# main.net
KiCad netlist of a schematic drawn in Altium Designer
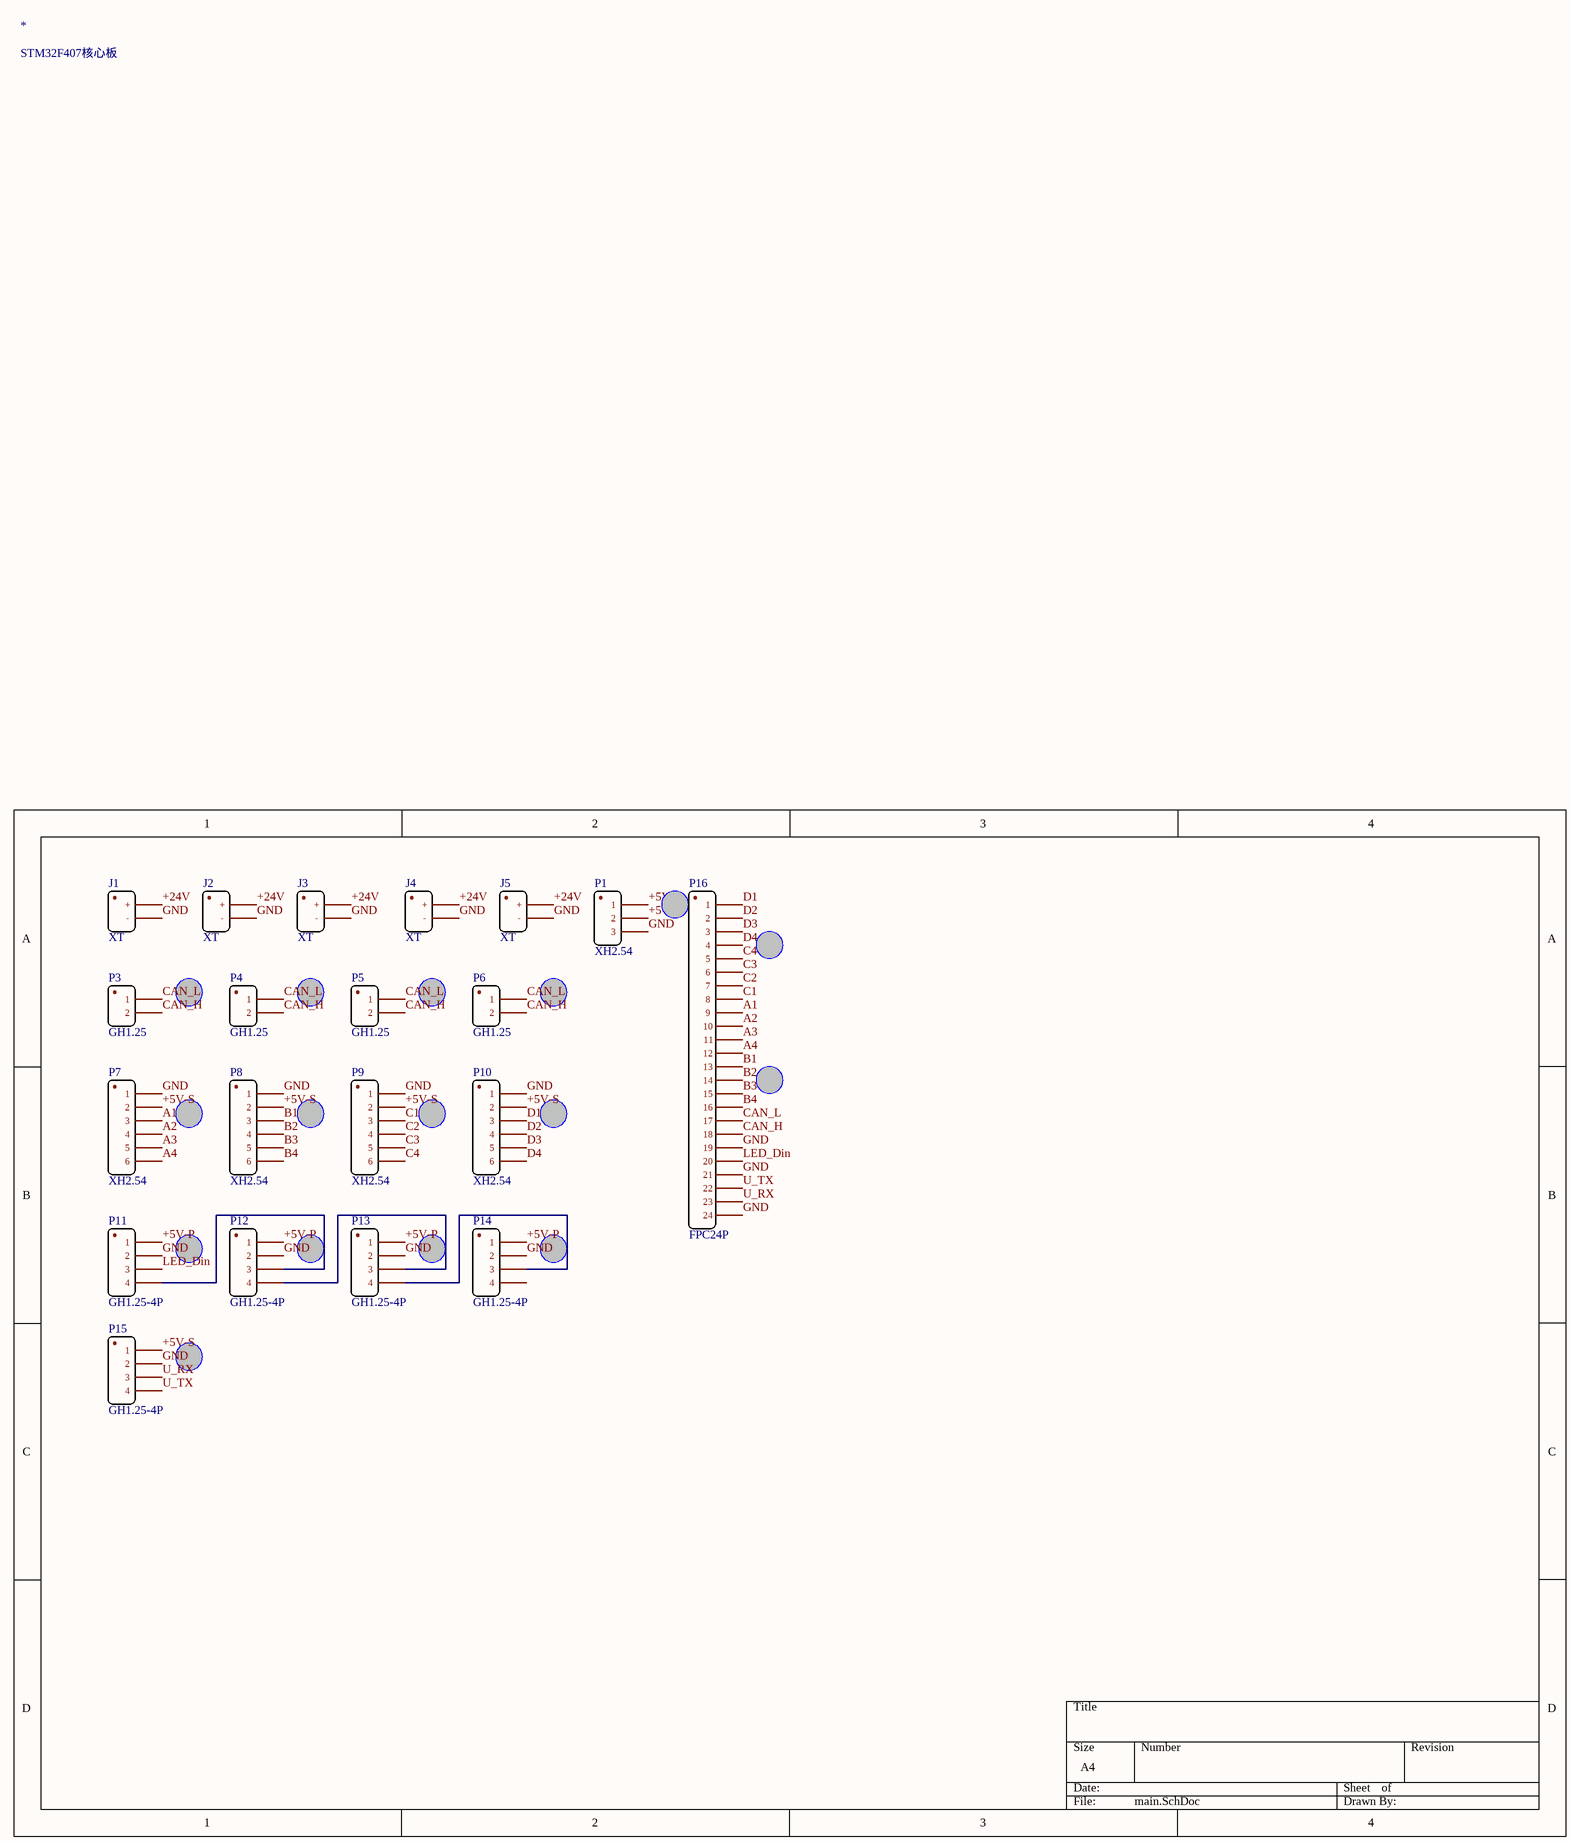
[diagram p0: main.SchDoc]

(export (version "E")
  (design (tool "Eeschema 10.0.6"))
  (components
    (comp (ref "*") (value "STM32F407核心板") (libsource (lib "模块库原理图") (part "STM32F407核心板")))
    (comp (ref "J1") (value "XT") (footprint "XT30-PW-F") (libsource (lib "接口库") (part "接口_XT")))
    (comp (ref "J2") (value "XT") (footprint "XT30-PW-F") (libsource (lib "接口库") (part "接口_XT")))
    (comp (ref "J3") (value "XT") (footprint "XT30-PW-F") (libsource (lib "接口库") (part "接口_XT")))
    (comp (ref "J4") (value "XT") (footprint "XT30-PW-F") (libsource (lib "接口库") (part "接口_XT")))
    (comp (ref "J5") (value "XT") (footprint "XT30-PW-M") (libsource (lib "接口库") (part "接口_XT")))
    (comp (ref "P1") (value "XH2.54") (footprint "XH2.54-PB-1*3") (libsource (lib "接口库") (part "接插件1*3")))
    (comp (ref "P3") (value "GH1.25") (footprint "GH1.25-PW-1*2") (libsource (lib "接口库") (part "接插件1*2")))
    (comp (ref "P4") (value "GH1.25") (footprint "GH1.25-PW-1*2") (libsource (lib "接口库") (part "接插件1*2")))
    (comp (ref "P5") (value "GH1.25") (footprint "GH1.25-PW-1*2") (libsource (lib "接口库") (part "接插件1*2")))
    (comp (ref "P6") (value "GH1.25") (footprint "GH1.25-PW-1*2") (libsource (lib "接口库") (part "接插件1*2")))
    (comp (ref "P7") (value "XH2.54") (footprint "XH2.54_AW_1*6") (libsource (lib "接口库") (part "接插件1*6")))
    (comp (ref "P8") (value "XH2.54") (footprint "XH2.54_AW_1*6") (libsource (lib "接口库") (part "接插件1*6")))
    (comp (ref "P9") (value "XH2.54") (footprint "XH2.54_AW_1*6") (libsource (lib "接口库") (part "接插件1*6")))
    (comp (ref "P10") (value "XH2.54") (footprint "XH2.54_AW_1*6") (libsource (lib "接口库") (part "接插件1*6")))
    (comp (ref "P11") (value "GH1.25-4P") (footprint "GH1.25-PW-1*4") (libsource (lib "接口库") (part "接插件1*4")))
    (comp (ref "P12") (value "GH1.25-4P") (footprint "GH1.25-PW-1*4") (libsource (lib "接口库") (part "接插件1*4")))
    (comp (ref "P13") (value "GH1.25-4P") (footprint "GH1.25-PW-1*4") (libsource (lib "接口库") (part "接插件1*4")))
    (comp (ref "P14") (value "GH1.25-4P") (footprint "GH1.25-PW-1*4") (libsource (lib "接口库") (part "接插件1*4")))
    (comp (ref "P15") (value "GH1.25-4P") (footprint "GH1.25-PW-1*4") (libsource (lib "接口库") (part "接插件1*4")))
    (comp (ref "P16") (value "FPC24P") (footprint "FPC0.5-WT-24P") (libsource (lib "接口库") (part "接插件1*24")))
  )
  (nets
    (net (code "1") (name "/+5V-P") (class "Default")
      (node (ref "P1") (pin "2") (pinfunction "2_2") (pintype "passive"))
      (node (ref "P11") (pin "1") (pinfunction "1_1") (pintype "passive"))
      (node (ref "P12") (pin "1") (pinfunction "1_1") (pintype "passive"))
      (node (ref "P13") (pin "1") (pinfunction "1_1") (pintype "passive"))
      (node (ref "P14") (pin "1") (pinfunction "1_1") (pintype "passive"))
    )
    (net (code "2") (name "/+5V-S") (class "Default")
      (node (ref "P1") (pin "1") (pinfunction "1_1") (pintype "passive"))
      (node (ref "P10") (pin "2") (pinfunction "2_2") (pintype "passive"))
      (node (ref "P15") (pin "1") (pinfunction "1_1") (pintype "passive"))
      (node (ref "P7") (pin "2") (pinfunction "2_2") (pintype "passive"))
      (node (ref "P8") (pin "2") (pinfunction "2_2") (pintype "passive"))
      (node (ref "P9") (pin "2") (pinfunction "2_2") (pintype "passive"))
    )
    (net (code "3") (name "/+24V") (class "Default")
      (node (ref "J1") (pin "1") (pinfunction "1_1") (pintype "passive"))
      (node (ref "J2") (pin "1") (pinfunction "1_1") (pintype "passive"))
      (node (ref "J3") (pin "1") (pinfunction "1_1") (pintype "passive"))
      (node (ref "J4") (pin "1") (pinfunction "1_1") (pintype "passive"))
      (node (ref "J5") (pin "1") (pinfunction "1_1") (pintype "passive"))
    )
    (net (code "4") (name "/A1") (class "Default")
      (node (ref "P16") (pin "9") (pinfunction "9_9") (pintype "passive"))
      (node (ref "P7") (pin "3") (pinfunction "3_3") (pintype "passive"))
    )
    (net (code "5") (name "/A2") (class "Default")
      (node (ref "P16") (pin "10") (pinfunction "10_10") (pintype "passive"))
      (node (ref "P7") (pin "4") (pinfunction "4_4") (pintype "passive"))
    )
    (net (code "6") (name "/A3") (class "Default")
      (node (ref "P16") (pin "11") (pinfunction "11_11") (pintype "passive"))
      (node (ref "P7") (pin "5") (pinfunction "5_5") (pintype "passive"))
    )
    (net (code "7") (name "/A4") (class "Default")
      (node (ref "P16") (pin "12") (pinfunction "12_12") (pintype "passive"))
      (node (ref "P7") (pin "6") (pinfunction "6_6") (pintype "passive"))
    )
    (net (code "8") (name "/B1") (class "Default")
      (node (ref "P16") (pin "13") (pinfunction "13_13") (pintype "passive"))
      (node (ref "P8") (pin "3") (pinfunction "3_3") (pintype "passive"))
    )
    (net (code "9") (name "/B2") (class "Default")
      (node (ref "P16") (pin "14") (pinfunction "14_14") (pintype "passive"))
      (node (ref "P8") (pin "4") (pinfunction "4_4") (pintype "passive"))
    )
    (net (code "10") (name "/B3") (class "Default")
      (node (ref "P16") (pin "15") (pinfunction "15_15") (pintype "passive"))
      (node (ref "P8") (pin "5") (pinfunction "5_5") (pintype "passive"))
    )
    (net (code "11") (name "/B4") (class "Default")
      (node (ref "P16") (pin "16") (pinfunction "16_16") (pintype "passive"))
      (node (ref "P8") (pin "6") (pinfunction "6_6") (pintype "passive"))
    )
    (net (code "12") (name "/C1") (class "Default")
      (node (ref "P16") (pin "8") (pinfunction "8_8") (pintype "passive"))
      (node (ref "P9") (pin "3") (pinfunction "3_3") (pintype "passive"))
    )
    (net (code "13") (name "/C2") (class "Default")
      (node (ref "P16") (pin "7") (pinfunction "7_7") (pintype "passive"))
      (node (ref "P9") (pin "4") (pinfunction "4_4") (pintype "passive"))
    )
    (net (code "14") (name "/C3") (class "Default")
      (node (ref "P16") (pin "6") (pinfunction "6_6") (pintype "passive"))
      (node (ref "P9") (pin "5") (pinfunction "5_5") (pintype "passive"))
    )
    (net (code "15") (name "/C4") (class "Default")
      (node (ref "P16") (pin "5") (pinfunction "5_5") (pintype "passive"))
      (node (ref "P9") (pin "6") (pinfunction "6_6") (pintype "passive"))
    )
    (net (code "16") (name "/CAN_H") (class "Default")
      (node (ref "P16") (pin "18") (pinfunction "18_18") (pintype "passive"))
      (node (ref "P3") (pin "2") (pinfunction "2_2") (pintype "passive"))
      (node (ref "P4") (pin "2") (pinfunction "2_2") (pintype "passive"))
      (node (ref "P5") (pin "2") (pinfunction "2_2") (pintype "passive"))
      (node (ref "P6") (pin "2") (pinfunction "2_2") (pintype "passive"))
    )
    (net (code "17") (name "/CAN_L") (class "Default")
      (node (ref "P16") (pin "17") (pinfunction "17_17") (pintype "passive"))
      (node (ref "P3") (pin "1") (pinfunction "1_1") (pintype "passive"))
      (node (ref "P4") (pin "1") (pinfunction "1_1") (pintype "passive"))
      (node (ref "P5") (pin "1") (pinfunction "1_1") (pintype "passive"))
      (node (ref "P6") (pin "1") (pinfunction "1_1") (pintype "passive"))
    )
    (net (code "18") (name "/D1") (class "Default")
      (node (ref "P10") (pin "3") (pinfunction "3_3") (pintype "passive"))
      (node (ref "P16") (pin "1") (pinfunction "1_1") (pintype "passive"))
    )
    (net (code "19") (name "/D2") (class "Default")
      (node (ref "P10") (pin "4") (pinfunction "4_4") (pintype "passive"))
      (node (ref "P16") (pin "2") (pinfunction "2_2") (pintype "passive"))
    )
    (net (code "20") (name "/D3") (class "Default")
      (node (ref "P10") (pin "5") (pinfunction "5_5") (pintype "passive"))
      (node (ref "P16") (pin "3") (pinfunction "3_3") (pintype "passive"))
    )
    (net (code "21") (name "/D4") (class "Default")
      (node (ref "P10") (pin "6") (pinfunction "6_6") (pintype "passive"))
      (node (ref "P16") (pin "4") (pinfunction "4_4") (pintype "passive"))
    )
    (net (code "22") (name "/GND") (class "Default")
      (node (ref "J1") (pin "2") (pinfunction "2_2") (pintype "passive"))
      (node (ref "J2") (pin "2") (pinfunction "2_2") (pintype "passive"))
      (node (ref "J3") (pin "2") (pinfunction "2_2") (pintype "passive"))
      (node (ref "J4") (pin "2") (pinfunction "2_2") (pintype "passive"))
      (node (ref "J5") (pin "2") (pinfunction "2_2") (pintype "passive"))
      (node (ref "P1") (pin "3") (pinfunction "3_3") (pintype "passive"))
      (node (ref "P10") (pin "1") (pinfunction "1_1") (pintype "passive"))
      (node (ref "P11") (pin "2") (pinfunction "2_2") (pintype "passive"))
      (node (ref "P12") (pin "2") (pinfunction "2_2") (pintype "passive"))
      (node (ref "P13") (pin "2") (pinfunction "2_2") (pintype "passive"))
      (node (ref "P14") (pin "2") (pinfunction "2_2") (pintype "passive"))
      (node (ref "P15") (pin "2") (pinfunction "2_2") (pintype "passive"))
      (node (ref "P16") (pin "19") (pinfunction "19_19") (pintype "passive"))
      (node (ref "P16") (pin "21") (pinfunction "21_21") (pintype "passive"))
      (node (ref "P16") (pin "24") (pinfunction "24_24") (pintype "passive"))
      (node (ref "P7") (pin "1") (pinfunction "1_1") (pintype "passive"))
      (node (ref "P8") (pin "1") (pinfunction "1_1") (pintype "passive"))
      (node (ref "P9") (pin "1") (pinfunction "1_1") (pintype "passive"))
    )
    (net (code "23") (name "/LED_Din") (class "Default")
      (node (ref "P11") (pin "3") (pinfunction "3_3") (pintype "passive"))
      (node (ref "P16") (pin "20") (pinfunction "20_20") (pintype "passive"))
    )
    (net (code "24") (name "/U_RX") (class "Default")
      (node (ref "P15") (pin "3") (pinfunction "3_3") (pintype "passive"))
      (node (ref "P16") (pin "23") (pinfunction "23_23") (pintype "passive"))
    )
    (net (code "25") (name "/U_TX") (class "Default")
      (node (ref "P15") (pin "4") (pinfunction "4_4") (pintype "passive"))
      (node (ref "P16") (pin "22") (pinfunction "22_22") (pintype "passive"))
    )
    (net (code "26") (name "Net-(P11-Pad4)") (class "Default")
      (node (ref "P11") (pin "4") (pinfunction "4_4") (pintype "passive"))
      (node (ref "P12") (pin "3") (pinfunction "3_3") (pintype "passive"))
    )
    (net (code "27") (name "Net-(P12-Pad4)") (class "Default")
      (node (ref "P12") (pin "4") (pinfunction "4_4") (pintype "passive"))
      (node (ref "P13") (pin "3") (pinfunction "3_3") (pintype "passive"))
    )
    (net (code "28") (name "Net-(P13-Pad4)") (class "Default")
      (node (ref "P13") (pin "4") (pinfunction "4_4") (pintype "passive"))
      (node (ref "P14") (pin "3") (pinfunction "3_3") (pintype "passive"))
    )
    (net (code "29") (name "unconnected-(P14-Pad4)") (class "Default")
      (node (ref "P14") (pin "4") (pinfunction "4_4") (pintype "passive"))
    )
  )
)
